# nes_visualization.net
KiCad netlist of a schematic drawn in EAGLE
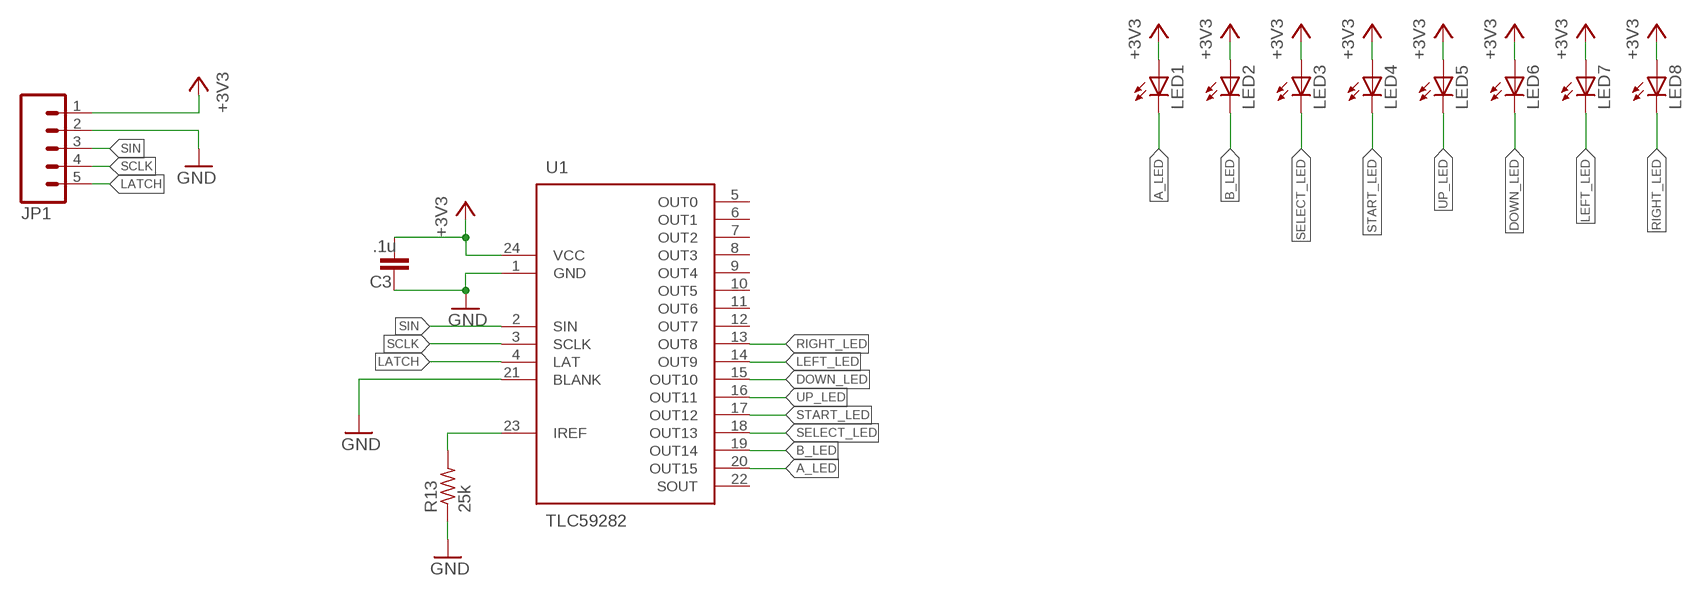
[diagram p0: schematic, sheet 1]

(export (version "E")
  (design (tool "Eeschema 10.0.6"))
  (components
    (comp (ref "C3")
      (value ".1u")
      (footprint "eagle-import:C0603")
      (libsource (lib "eagle-import") (part "C-EUC0603"))
    )
    (comp (ref "JP1")
      (value "M05PTH")
      (footprint "eagle-import:1X05")
      (libsource (lib "eagle-import") (part "M05PTH"))
    )
    (comp (ref "LED1")
      (value "LED5MM")
      (footprint "eagle-import:LED5MM")
      (libsource (lib "eagle-import") (part "LED5MM"))
    )
    (comp (ref "LED2")
      (value "LED5MM")
      (footprint "eagle-import:LED5MM")
      (libsource (lib "eagle-import") (part "LED5MM"))
    )
    (comp (ref "LED3")
      (value "LED3MM")
      (footprint "eagle-import:LED3MM")
      (libsource (lib "eagle-import") (part "LED3MM"))
    )
    (comp (ref "LED4")
      (value "LED3MM")
      (footprint "eagle-import:LED3MM")
      (libsource (lib "eagle-import") (part "LED3MM"))
    )
    (comp (ref "LED5")
      (value "LED5MM")
      (footprint "eagle-import:LED5MM")
      (libsource (lib "eagle-import") (part "LED5MM"))
    )
    (comp (ref "LED6")
      (value "LED5MM")
      (footprint "eagle-import:LED5MM")
      (libsource (lib "eagle-import") (part "LED5MM"))
    )
    (comp (ref "LED7")
      (value "LED5MM")
      (footprint "eagle-import:LED5MM")
      (libsource (lib "eagle-import") (part "LED5MM"))
    )
    (comp (ref "LED8")
      (value "LED5MM")
      (footprint "eagle-import:LED5MM")
      (libsource (lib "eagle-import") (part "LED5MM"))
    )
    (comp (ref "R13")
      (value "25k")
      (footprint "eagle-import:R0805")
      (libsource (lib "eagle-import") (part "R-US_R0805"))
    )
    (comp (ref "U1")
      (value "TLC59282")
      (footprint "eagle-import:R-PDSO-G24")
      (libsource (lib "eagle-import") (part "TLC59282"))
    )
  )
  (nets
    (net (code "1") (name "+3V3") (class "Default")
      (node (ref "C3") (pin "1") (pinfunction "1_1") (pintype "passive"))
      (node (ref "JP1") (pin "1") (pinfunction "1_1") (pintype "passive"))
      (node (ref "LED1") (pin "A") (pinfunction "A_A") (pintype "passive"))
      (node (ref "LED2") (pin "A") (pinfunction "A_A") (pintype "passive"))
      (node (ref "LED3") (pin "A") (pinfunction "A_A") (pintype "passive"))
      (node (ref "LED4") (pin "A") (pinfunction "A_A") (pintype "passive"))
      (node (ref "LED5") (pin "A") (pinfunction "A_A") (pintype "passive"))
      (node (ref "LED6") (pin "A") (pinfunction "A_A") (pintype "passive"))
      (node (ref "LED7") (pin "A") (pinfunction "A_A") (pintype "passive"))
      (node (ref "LED8") (pin "A") (pinfunction "A_A") (pintype "passive"))
      (node (ref "U1") (pin "24") (pinfunction "VCC_24") (pintype "input"))
    )
    (net (code "2") (name "A_LED") (class "Default")
      (node (ref "LED1") (pin "K") (pinfunction "C_K") (pintype "passive"))
      (node (ref "U1") (pin "20") (pinfunction "OUT15_20") (pintype "input"))
    )
    (net (code "3") (name "B_LED") (class "Default")
      (node (ref "LED2") (pin "K") (pinfunction "C_K") (pintype "passive"))
      (node (ref "U1") (pin "19") (pinfunction "OUT14_19") (pintype "input"))
    )
    (net (code "4") (name "DOWN_LED") (class "Default")
      (node (ref "LED6") (pin "K") (pinfunction "C_K") (pintype "passive"))
      (node (ref "U1") (pin "15") (pinfunction "OUT10_15") (pintype "input"))
    )
    (net (code "5") (name "GND") (class "Default")
      (node (ref "C3") (pin "2") (pinfunction "2_2") (pintype "passive"))
      (node (ref "JP1") (pin "2") (pinfunction "2_2") (pintype "passive"))
      (node (ref "R13") (pin "1") (pinfunction "1_1") (pintype "passive"))
      (node (ref "U1") (pin "1") (pinfunction "GND_1") (pintype "input"))
      (node (ref "U1") (pin "21") (pinfunction "BLANK_21") (pintype "input"))
    )
    (net (code "6") (name "LATCH") (class "Default")
      (node (ref "JP1") (pin "5") (pinfunction "5_5") (pintype "passive"))
      (node (ref "U1") (pin "4") (pinfunction "LAT_4") (pintype "input"))
    )
    (net (code "7") (name "LEFT_LED") (class "Default")
      (node (ref "LED7") (pin "K") (pinfunction "C_K") (pintype "passive"))
      (node (ref "U1") (pin "14") (pinfunction "OUT9_14") (pintype "input"))
    )
    (net (code "8") (name "Net-(U1-IREF)") (class "Default")
      (node (ref "R13") (pin "2") (pinfunction "2_2") (pintype "passive"))
      (node (ref "U1") (pin "23") (pinfunction "IREF_23") (pintype "input"))
    )
    (net (code "9") (name "RIGHT_LED") (class "Default")
      (node (ref "LED8") (pin "K") (pinfunction "C_K") (pintype "passive"))
      (node (ref "U1") (pin "13") (pinfunction "OUT8_13") (pintype "input"))
    )
    (net (code "10") (name "SCLK") (class "Default")
      (node (ref "JP1") (pin "4") (pinfunction "4_4") (pintype "passive"))
      (node (ref "U1") (pin "3") (pinfunction "SCLK_3") (pintype "input"))
    )
    (net (code "11") (name "SELECT_LED") (class "Default")
      (node (ref "LED3") (pin "K") (pinfunction "C_K") (pintype "passive"))
      (node (ref "U1") (pin "18") (pinfunction "OUT13_18") (pintype "input"))
    )
    (net (code "12") (name "SIN") (class "Default")
      (node (ref "JP1") (pin "3") (pinfunction "3_3") (pintype "passive"))
      (node (ref "U1") (pin "2") (pinfunction "SIN_2") (pintype "input"))
    )
    (net (code "13") (name "START_LED") (class "Default")
      (node (ref "LED4") (pin "K") (pinfunction "C_K") (pintype "passive"))
      (node (ref "U1") (pin "17") (pinfunction "OUT12_17") (pintype "input"))
    )
    (net (code "14") (name "UP_LED") (class "Default")
      (node (ref "LED5") (pin "K") (pinfunction "C_K") (pintype "passive"))
      (node (ref "U1") (pin "16") (pinfunction "OUT11_16") (pintype "input"))
    )
    (net (code "15") (name "unconnected-(U1-OUT0-Pad5)") (class "Default")
      (node (ref "U1") (pin "5") (pinfunction "OUT0_5") (pintype "input"))
    )
    (net (code "16") (name "unconnected-(U1-OUT1-Pad6)") (class "Default")
      (node (ref "U1") (pin "6") (pinfunction "OUT1_6") (pintype "input"))
    )
    (net (code "17") (name "unconnected-(U1-OUT2-Pad7)") (class "Default")
      (node (ref "U1") (pin "7") (pinfunction "OUT2_7") (pintype "input"))
    )
    (net (code "18") (name "unconnected-(U1-OUT3-Pad8)") (class "Default")
      (node (ref "U1") (pin "8") (pinfunction "OUT3_8") (pintype "input"))
    )
    (net (code "19") (name "unconnected-(U1-OUT4-Pad9)") (class "Default")
      (node (ref "U1") (pin "9") (pinfunction "OUT4_9") (pintype "input"))
    )
    (net (code "20") (name "unconnected-(U1-OUT5-Pad10)") (class "Default")
      (node (ref "U1") (pin "10") (pinfunction "OUT5_10") (pintype "input"))
    )
    (net (code "21") (name "unconnected-(U1-OUT6-Pad11)") (class "Default")
      (node (ref "U1") (pin "11") (pinfunction "OUT6_11") (pintype "input"))
    )
    (net (code "22") (name "unconnected-(U1-OUT7-Pad12)") (class "Default")
      (node (ref "U1") (pin "12") (pinfunction "OUT7_12") (pintype "input"))
    )
    (net (code "23") (name "unconnected-(U1-SOUT-Pad22)") (class "Default")
      (node (ref "U1") (pin "22") (pinfunction "SOUT_22") (pintype "input"))
    )
  )
)
